# Sensor_Bar_2_0_regulators.net
KiCad netlist of a schematic drawn in Altium Designer
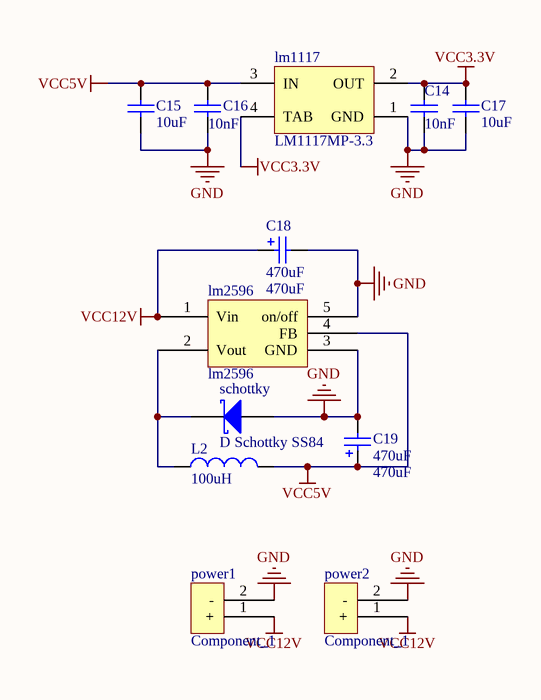
[diagram p0: Sensor Bar 2.0 regulators.SchDoc]

(export (version "E")
  (design (tool "Eeschema 10.0.6"))
  (components
    (comp (ref "C14")
      (value "10nF")
      (footprint "CC2012-0805")
      (description "Capacitor (Semiconductor SIM Model)")
      (fields (field (name "PUBLISHER") "Altium Limited"))
      (libsource (lib "Motorcontrol2.0") (part "Cap Semi"))
    )
    (comp (ref "C15")
      (value "10uF")
      (footprint "CC3225-1210")
      (description "Capacitor (Semiconductor SIM Model)")
      (fields (field (name "PUBLISHER") "Altium Limited"))
      (libsource (lib "Motorcontrol2.0") (part "Cap Semi"))
    )
    (comp (ref "C16")
      (value "10nF")
      (footprint "CC2012-0805")
      (description "Capacitor (Semiconductor SIM Model)")
      (fields (field (name "PUBLISHER") "Altium Limited"))
      (libsource (lib "Motorcontrol2.0") (part "Cap Semi"))
    )
    (comp (ref "C17")
      (value "10uF")
      (footprint "CC3225-1210")
      (description "Capacitor (Semiconductor SIM Model)")
      (fields (field (name "PUBLISHER") "Altium Limited"))
      (libsource (lib "Motorcontrol2.0") (part "Cap Semi"))
    )
    (comp (ref "C18")
      (value "470uF")
      (footprint "470UF/50V")
      (description "Polarized Capacitor (Surface Mount)")
      (fields (field (name "ALTIUM_VALUE") "470uF") (field (name "PUBLISHER") "Altium Limited"))
      (libsource (lib "Motorcontrol2.0") (part "Cap Pol3"))
    )
    (comp (ref "C19")
      (value "470uF")
      (footprint "470UF/50V")
      (description "Polarized Capacitor (Surface Mount)")
      (fields (field (name "ALTIUM_VALUE") "470uF") (field (name "PUBLISHER") "Altium Limited"))
      (libsource (lib "Motorcontrol2.0") (part "Cap Pol3"))
    )
    (comp (ref "L2")
      (value "100uH")
      (footprint "MSS1260")
      (description "Inductor")
      (fields (field (name "PUBLISHER") "Altium Limited"))
      (libsource (lib "Motorcontrol2.0") (part "Inductor"))
    )
    (comp (ref "lm1117")
      (value "LM1117MP-3.3")
      (footprint "MP04A_N")
      (description "800mA Low-Dropout Linear Regulator")
      (fields
        (field (name "MANUFACTURER") "National Semiconductor")
        (field (name "DIGIKEYPARTNUMBER") "LM1117MP-3.3CT-ND")
        (field (name "PUBLISHER") "Altium Limited")
      )
      (libsource (lib "Motorcontrol2.0") (part "LM1117MP-3.3"))
    )
    (comp (ref "lm2596")
      (value "lm2596")
      (footprint "lm2596")
      (libsource (lib "lm2596") (part "Component_1"))
    )
    (comp (ref "power1")
      (value "Component_1")
      (footprint "PCBComponent_1")
      (libsource (lib "small power") (part "Component_1"))
    )
    (comp (ref "power2")
      (value "Component_1")
      (footprint "PCBComponent_1")
      (libsource (lib "small power") (part "Component_1"))
    )
    (comp (ref "schottky")
      (value "D Schottky SS84")
      (footprint "sch_diode")
      (description "Schottky Diode")
      (fields (field (name "PUBLISHER") "Altium Limited"))
      (libsource (lib "肖特基二极管") (part "D Schottky"))
    )
  )
  (nets
    (net (code "1") (name "GND") (class "Default")
      (node (ref "C14") (pin "1") (pinfunction "1_1") (pintype "passive"))
      (node (ref "C15") (pin "2") (pinfunction "2_2") (pintype "passive"))
      (node (ref "C16") (pin "1") (pinfunction "1_1") (pintype "passive"))
      (node (ref "C17") (pin "2") (pinfunction "2_2") (pintype "passive"))
      (node (ref "C18") (pin "2") (pinfunction "2_2") (pintype "passive"))
      (node (ref "C19") (pin "2") (pinfunction "2_2") (pintype "passive"))
      (node (ref "lm1117") (pin "1") (pinfunction "GND_1") (pintype "power_in"))
      (node (ref "lm2596") (pin "3") (pinfunction "GND_3") (pintype "passive"))
      (node (ref "lm2596") (pin "5") (pinfunction "on/off_5") (pintype "passive"))
      (node (ref "power1") (pin "2") (pinfunction "-_2") (pintype "passive"))
      (node (ref "power2") (pin "2") (pinfunction "-_2") (pintype "passive"))
      (node (ref "schottky") (pin "2") (pinfunction "B_2") (pintype "passive"))
    )
    (net (code "2") (name "Net-(lm2596-Vout)") (class "Default")
      (node (ref "L2") (pin "1") (pinfunction "1_1") (pintype "passive"))
      (node (ref "lm2596") (pin "2") (pinfunction "Vout_2") (pintype "passive"))
      (node (ref "schottky") (pin "1") (pinfunction "A_1") (pintype "passive"))
    )
    (net (code "3") (name "VCC3.3V") (class "Default")
      (node (ref "C14") (pin "2") (pinfunction "2_2") (pintype "passive"))
      (node (ref "C17") (pin "1") (pinfunction "1_1") (pintype "passive"))
      (node (ref "lm1117") (pin "2") (pinfunction "OUT_2") (pintype "power_in"))
      (node (ref "lm1117") (pin "4") (pinfunction "TAB_4") (pintype "power_in"))
    )
    (net (code "4") (name "VCC5V") (class "Default")
      (node (ref "C15") (pin "1") (pinfunction "1_1") (pintype "passive"))
      (node (ref "C16") (pin "2") (pinfunction "2_2") (pintype "passive"))
      (node (ref "C19") (pin "1") (pinfunction "1_1") (pintype "passive"))
      (node (ref "L2") (pin "2") (pinfunction "2_2") (pintype "passive"))
      (node (ref "lm1117") (pin "3") (pinfunction "IN_3") (pintype "power_in"))
      (node (ref "lm2596") (pin "4") (pinfunction "FB_4") (pintype "passive"))
    )
    (net (code "5") (name "VCC12V") (class "Default")
      (node (ref "C18") (pin "1") (pinfunction "1_1") (pintype "passive"))
      (node (ref "lm2596") (pin "1") (pinfunction "Vin_1") (pintype "passive"))
      (node (ref "power1") (pin "1") (pinfunction "+_1") (pintype "passive"))
      (node (ref "power2") (pin "1") (pinfunction "+_1") (pintype "passive"))
    )
  )
)
